# Slinea_velocistaEdu.net
KiCad netlist of a schematic drawn in EAGLE
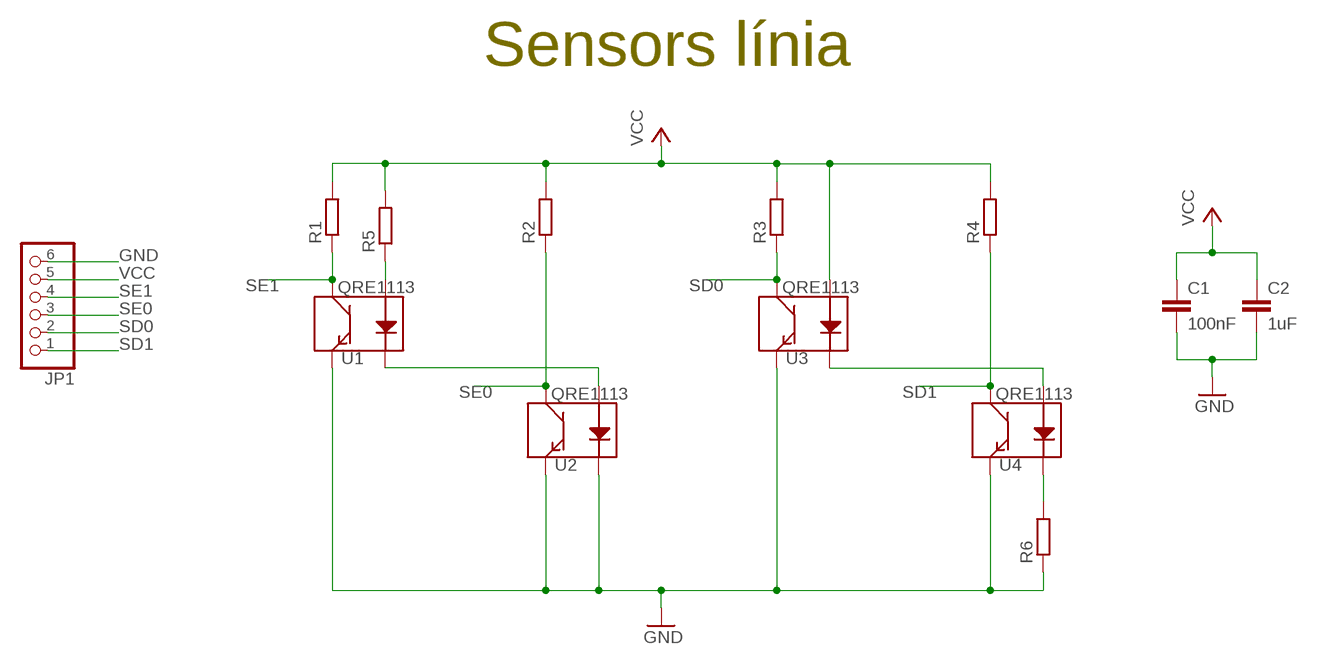
[diagram p0: schematic, sheet 1]

(export (version "E")
  (design (tool "Eeschema 10.0.6"))
  (components
    (comp (ref "C1")
      (value "100nF")
      (footprint "eagle-import:C0805")
      (libsource (lib "eagle-import") (part "C-EUC0805"))
    )
    (comp (ref "C2")
      (value "1uF")
      (footprint "eagle-import:C0805")
      (libsource (lib "eagle-import") (part "C-EUC0805"))
    )
    (comp (ref "JP1")
      (value "PINHD-1X6")
      (footprint "eagle-import:1X06")
      (libsource (lib "eagle-import") (part "PINHD-1X6"))
    )
    (comp (ref "R1")
      (value "R-EU_M0805")
      (footprint "eagle-import:M0805@1")
      (libsource (lib "eagle-import") (part "resistor_R-EU_M0805"))
    )
    (comp (ref "R2")
      (value "R-EU_M0805")
      (footprint "eagle-import:M0805")
      (libsource (lib "eagle-import") (part "R-EU_M0805"))
    )
    (comp (ref "R3")
      (value "R-EU_M0805")
      (footprint "eagle-import:M0805")
      (libsource (lib "eagle-import") (part "R-EU_M0805"))
    )
    (comp (ref "R4")
      (value "R-EU_M0805")
      (footprint "eagle-import:M0805")
      (libsource (lib "eagle-import") (part "R-EU_M0805"))
    )
    (comp (ref "R5")
      (value "R-EU_M0805")
      (footprint "eagle-import:M0805")
      (libsource (lib "eagle-import") (part "R-EU_M0805"))
    )
    (comp (ref "R6")
      (value "R-EU_M0805")
      (footprint "eagle-import:M0805")
      (libsource (lib "eagle-import") (part "R-EU_M0805"))
    )
    (comp (ref "U1")
      (value "QRE1113")
      (footprint "eagle-import:QRE1113")
      (libsource (lib "eagle-import") (part "QRE1113"))
    )
    (comp (ref "U2")
      (value "QRE1113")
      (footprint "eagle-import:QRE1113")
      (libsource (lib "eagle-import") (part "QRE1113"))
    )
    (comp (ref "U3")
      (value "QRE1113")
      (footprint "eagle-import:QRE1113")
      (libsource (lib "eagle-import") (part "QRE1113"))
    )
    (comp (ref "U4")
      (value "QRE1113")
      (footprint "eagle-import:QRE1113")
      (libsource (lib "eagle-import") (part "QRE1113"))
    )
  )
  (nets
    (net (code "1") (name "/SD0") (class "Default")
      (node (ref "JP1") (pin "2") (pinfunction "2_2") (pintype "passive"))
      (node (ref "R3") (pin "1") (pinfunction "1_1") (pintype "passive"))
      (node (ref "U3") (pin "3") (pinfunction "C_3") (pintype "bidirectional"))
    )
    (net (code "2") (name "/SD1") (class "Default")
      (node (ref "JP1") (pin "1") (pinfunction "1_1") (pintype "passive"))
      (node (ref "R4") (pin "1") (pinfunction "1_1") (pintype "passive"))
      (node (ref "U4") (pin "3") (pinfunction "C_3") (pintype "bidirectional"))
    )
    (net (code "3") (name "/SE0") (class "Default")
      (node (ref "JP1") (pin "3") (pinfunction "3_3") (pintype "passive"))
      (node (ref "R2") (pin "1") (pinfunction "1_1") (pintype "passive"))
      (node (ref "U2") (pin "3") (pinfunction "C_3") (pintype "bidirectional"))
    )
    (net (code "4") (name "/SE1") (class "Default")
      (node (ref "JP1") (pin "4") (pinfunction "4_4") (pintype "passive"))
      (node (ref "R1") (pin "1") (pinfunction "1_1") (pintype "passive"))
      (node (ref "U1") (pin "3") (pinfunction "C_3") (pintype "bidirectional"))
    )
    (net (code "5") (name "GND") (class "Default")
      (node (ref "C1") (pin "2") (pinfunction "2_2") (pintype "passive"))
      (node (ref "C2") (pin "2") (pinfunction "2_2") (pintype "passive"))
      (node (ref "JP1") (pin "6") (pinfunction "6_6") (pintype "passive"))
      (node (ref "R6") (pin "1") (pinfunction "1_1") (pintype "passive"))
      (node (ref "U1") (pin "4") (pinfunction "E_4") (pintype "bidirectional"))
      (node (ref "U2") (pin "2") (pinfunction "K_2") (pintype "bidirectional"))
      (node (ref "U2") (pin "4") (pinfunction "E_4") (pintype "bidirectional"))
      (node (ref "U3") (pin "4") (pinfunction "E_4") (pintype "bidirectional"))
      (node (ref "U4") (pin "4") (pinfunction "E_4") (pintype "bidirectional"))
    )
    (net (code "6") (name "Net-(U1-A)") (class "Default")
      (node (ref "R5") (pin "1") (pinfunction "1_1") (pintype "passive"))
      (node (ref "U1") (pin "1") (pinfunction "A_1") (pintype "bidirectional"))
    )
    (net (code "7") (name "Net-(U1-K)") (class "Default")
      (node (ref "U1") (pin "2") (pinfunction "K_2") (pintype "bidirectional"))
      (node (ref "U2") (pin "1") (pinfunction "A_1") (pintype "bidirectional"))
    )
    (net (code "8") (name "Net-(U3-K)") (class "Default")
      (node (ref "U3") (pin "2") (pinfunction "K_2") (pintype "bidirectional"))
      (node (ref "U4") (pin "1") (pinfunction "A_1") (pintype "bidirectional"))
    )
    (net (code "9") (name "Net-(U4-K)") (class "Default")
      (node (ref "R6") (pin "2") (pinfunction "2_2") (pintype "passive"))
      (node (ref "U4") (pin "2") (pinfunction "K_2") (pintype "bidirectional"))
    )
    (net (code "10") (name "VCC") (class "Default")
      (node (ref "C1") (pin "1") (pinfunction "1_1") (pintype "passive"))
      (node (ref "C2") (pin "1") (pinfunction "1_1") (pintype "passive"))
      (node (ref "JP1") (pin "5") (pinfunction "5_5") (pintype "passive"))
      (node (ref "R1") (pin "2") (pinfunction "2_2") (pintype "passive"))
      (node (ref "R2") (pin "2") (pinfunction "2_2") (pintype "passive"))
      (node (ref "R3") (pin "2") (pinfunction "2_2") (pintype "passive"))
      (node (ref "R4") (pin "2") (pinfunction "2_2") (pintype "passive"))
      (node (ref "R5") (pin "2") (pinfunction "2_2") (pintype "passive"))
      (node (ref "U3") (pin "1") (pinfunction "A_1") (pintype "bidirectional"))
    )
  )
)
